# DA2_SCH_PAGE2.net
KiCad netlist of a schematic drawn in Altium Designer
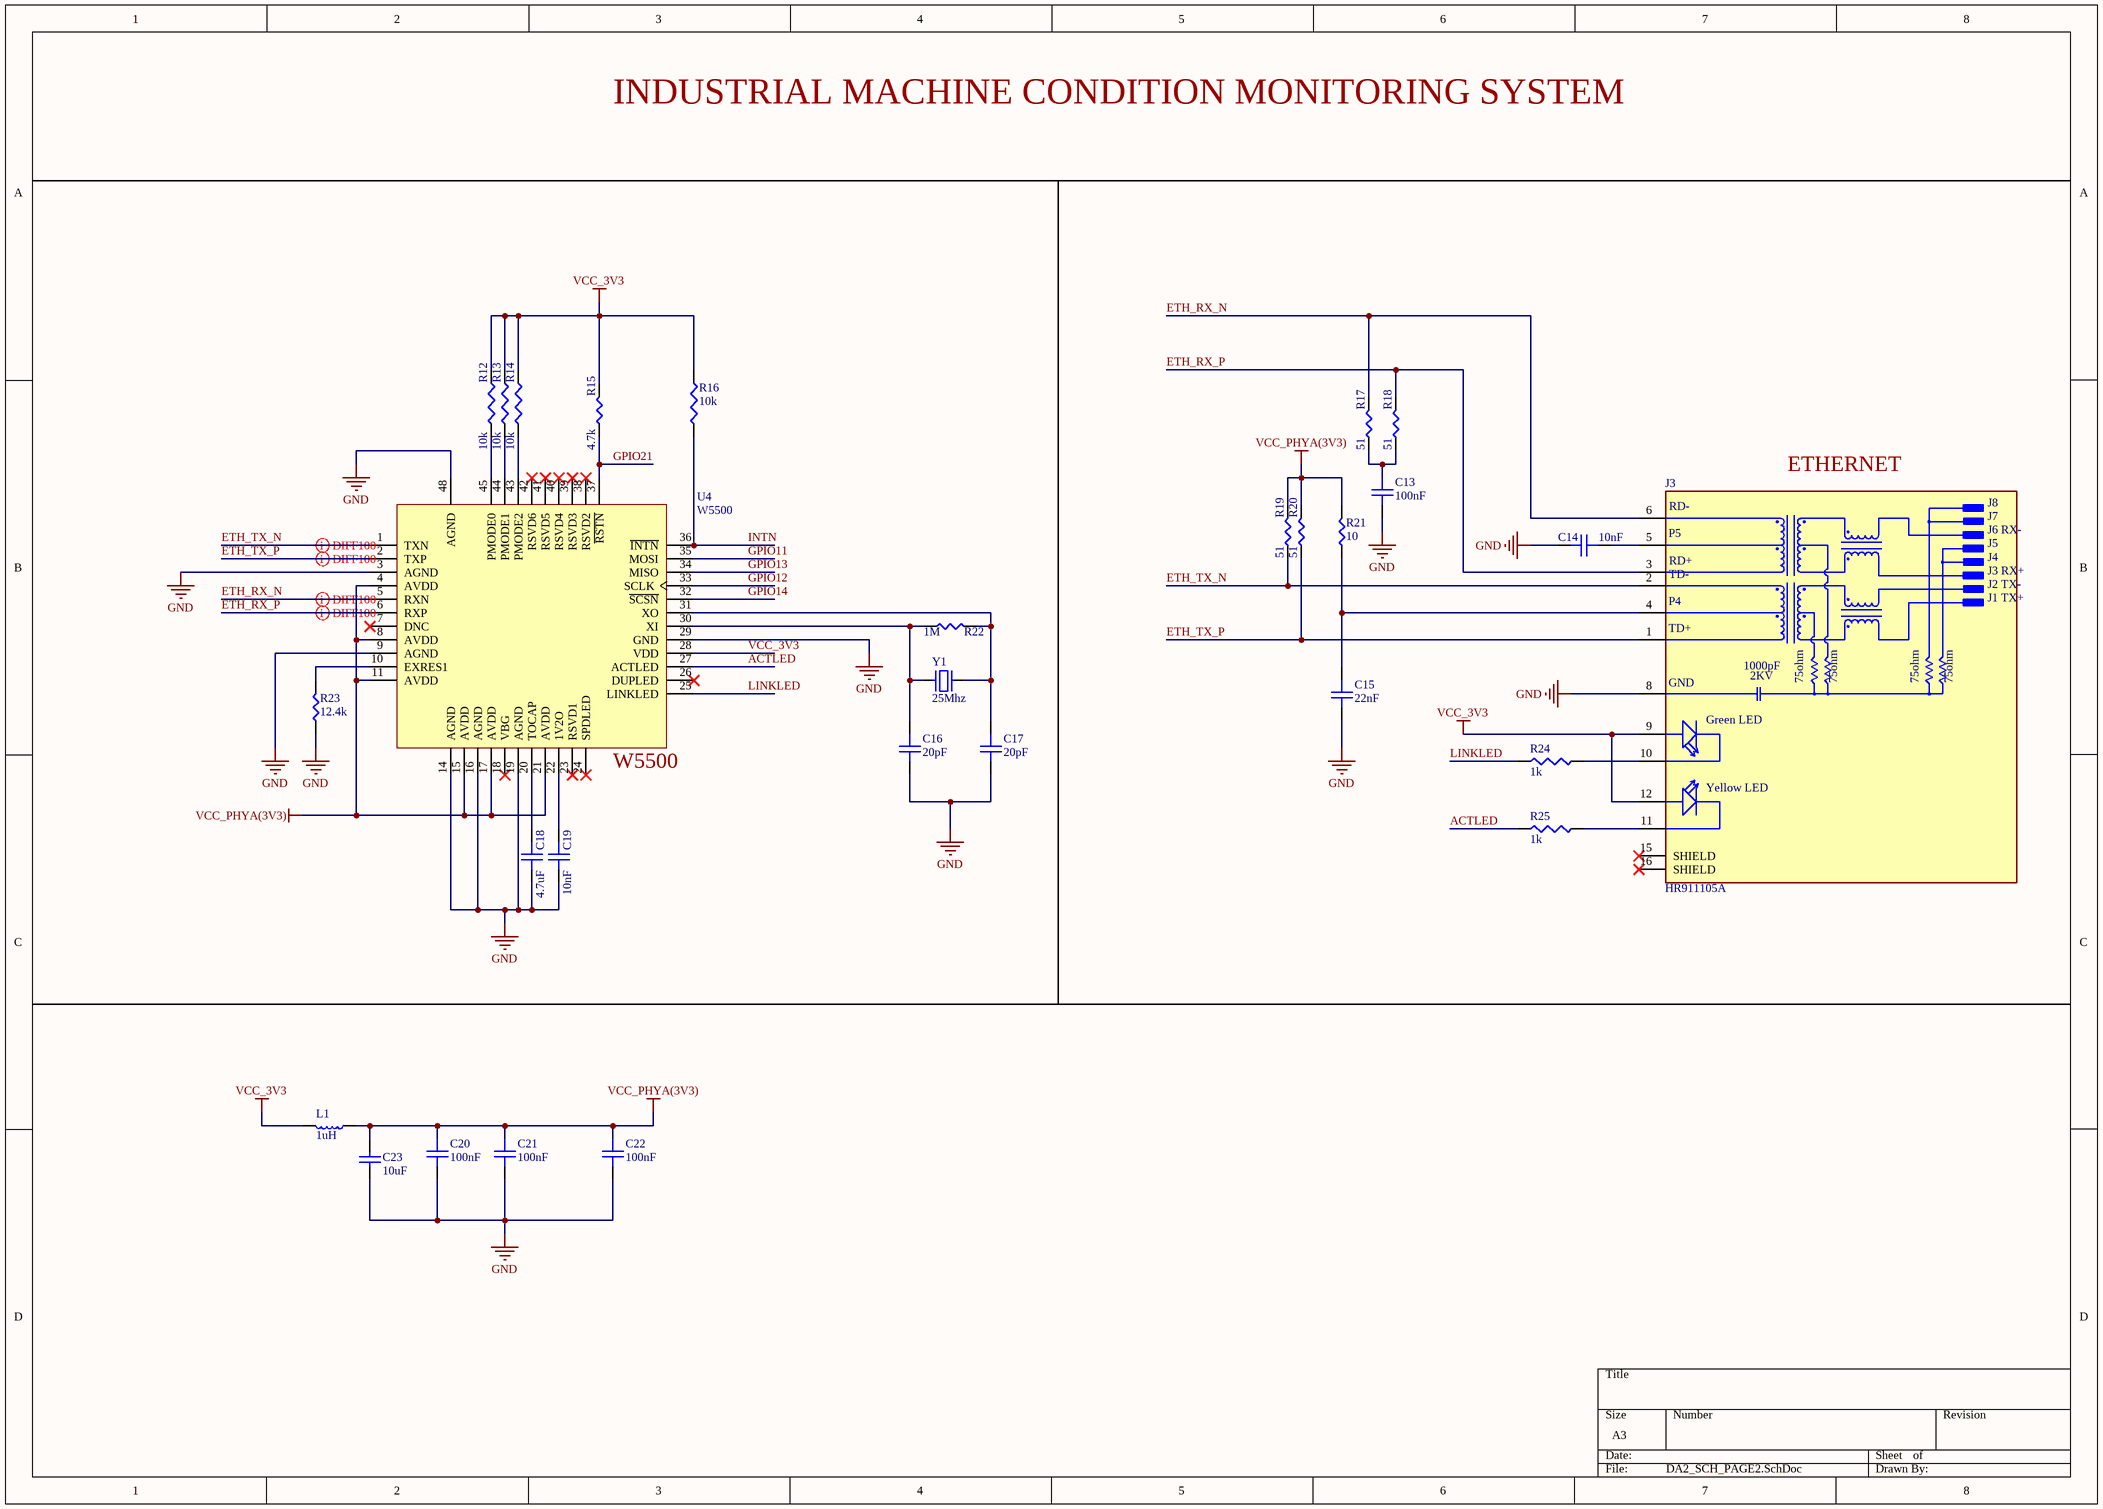
[diagram p0: DA2_SCH_PAGE2.SchDoc]

(export (version "E")
  (design (tool "Eeschema 10.0.6"))
  (components
    (comp (ref "C13")
      (value "100nF")
      (footprint "tu 0805")
      (description "Dán 0805")
      (libsource (lib "DA2") (part "Tu 100nF"))
    )
    (comp (ref "C14")
      (value "10nF")
      (footprint "tu 0805")
      (description "Dán 0805")
      (libsource (lib "DA2") (part "Tu 10nF"))
    )
    (comp (ref "C15")
      (value "22nF")
      (footprint "tu 0805")
      (description "Dán 0805")
      (libsource (lib "DA2") (part "Tu 22nF"))
    )
    (comp (ref "C16")
      (value "20pF")
      (footprint "tu 0805")
      (description "Dán 0805")
      (libsource (lib "DA2") (part "Tu  20pF"))
    )
    (comp (ref "C17")
      (value "20pF")
      (footprint "tu 0805")
      (description "Dán 0805")
      (libsource (lib "DA2") (part "Tu  20pF"))
    )
    (comp (ref "C18")
      (value "4.7uF")
      (footprint "Tu 0805")
      (description "Dán 0805")
      (libsource (lib "DA2") (part "Tu 4.7uF"))
    )
    (comp (ref "C19")
      (value "10nF")
      (footprint "tu 0805")
      (description "Dán 0805")
      (libsource (lib "DA2") (part "Tu 10nF"))
    )
    (comp (ref "C20")
      (value "100nF")
      (footprint "tu 0805")
      (description "Dán 0805")
      (libsource (lib "DA2") (part "Tu 100nF"))
    )
    (comp (ref "C21")
      (value "100nF")
      (footprint "tu 0805")
      (description "Dán 0805")
      (libsource (lib "DA2") (part "Tu 100nF"))
    )
    (comp (ref "C22")
      (value "100nF")
      (footprint "tu 0805")
      (description "Dán 0805")
      (libsource (lib "DA2") (part "Tu 100nF"))
    )
    (comp (ref "C23")
      (value "10uF")
      (footprint "Tu 0805")
      (description "Dán 0805")
      (fields
        (field (name "MANUFACTURER") "Samsung Electro-Mechanics")
        (field (name "MANUFACTURER PART NUMBER") "CL05A106MP5NUNC")
      )
      (libsource (lib "DA2") (part "Tu 10uF"))
    )
    (comp (ref "J3")
      (value "HR911105A")
      (footprint "HANRUN_HR911105A")
      (description "DIP RJ45 Connector;")
      (fields (field (name "MF") "hanrun"))
      (libsource (lib "Schlib1") (part "HR911105A"))
    )
    (comp (ref "L1")
      (value "1uH")
      (footprint "Tu 0805")
      (description "Dán 0805")
      (libsource (lib "DA2") (part "Cuon Cam 1uH"))
    )
    (comp (ref "R12")
      (value "10k")
      (footprint "Tro SMD 0805")
      (description "Dán 0805")
      (fields
        (field (name "MANUFACTURER") "Yageo Group")
        (field (name "MANUFACTURER PART NUMBER") "RC0402FR-0710KL")
      )
      (libsource (lib "DA2") (part "Tro 10k"))
    )
    (comp (ref "R13")
      (value "10k")
      (footprint "Tro SMD 0805")
      (description "Dán 0805")
      (fields
        (field (name "MANUFACTURER") "Yageo Group")
        (field (name "MANUFACTURER PART NUMBER") "RC0402FR-0710KL")
      )
      (libsource (lib "DA2") (part "Tro 10k"))
    )
    (comp (ref "R14")
      (value "10k")
      (footprint "Tro SMD 0805")
      (description "Dán 0805")
      (fields
        (field (name "MANUFACTURER") "Yageo Group")
        (field (name "MANUFACTURER PART NUMBER") "RC0402FR-0710KL")
      )
      (libsource (lib "DA2") (part "Tro 10k"))
    )
    (comp (ref "R15")
      (value "4.7k")
      (footprint "tro smd 0805")
      (description "Dán 0805")
      (libsource (lib "DA2") (part "Tro 4.7k"))
    )
    (comp (ref "R16")
      (value "10k")
      (footprint "Tro SMD 0805")
      (description "Dán 0805")
      (fields
        (field (name "MANUFACTURER") "Yageo Group")
        (field (name "MANUFACTURER PART NUMBER") "RC0402FR-0710KL")
      )
      (libsource (lib "DA2") (part "Tro 10k"))
    )
    (comp (ref "R17")
      (value "51")
      (footprint "tro smd 0805")
      (description "Dán 0805")
      (libsource (lib "DA2") (part "Tro 51"))
    )
    (comp (ref "R18")
      (value "51")
      (footprint "tro smd 0805")
      (description "Dán 0805")
      (libsource (lib "DA2") (part "Tro 51"))
    )
    (comp (ref "R19")
      (value "51")
      (footprint "tro smd 0805")
      (description "Dán 0805")
      (libsource (lib "DA2") (part "Tro 51"))
    )
    (comp (ref "R20")
      (value "51")
      (footprint "tro smd 0805")
      (description "Dán 0805")
      (libsource (lib "DA2") (part "Tro 51"))
    )
    (comp (ref "R21")
      (value "10")
      (footprint "tro smd 0805")
      (description "Dán 0805")
      (libsource (lib "DA2") (part "Tro 10"))
    )
    (comp (ref "R22")
      (value "1M")
      (footprint "tro smd 0805")
      (description "Dán 0805")
      (libsource (lib "DA2") (part "Tro 1M"))
    )
    (comp (ref "R23")
      (value "12.4k")
      (footprint "tro smd 0805")
      (description "Dán 0805")
      (libsource (lib "DA2") (part "Tro 12.4k"))
    )
    (comp (ref "R24")
      (value "1k")
      (footprint "Tro SMD 0805")
      (description "Dán 0805")
      (fields
        (field (name "MANUFACTURER") "Yageo Group")
        (field (name "MANUFACTURER PART NUMBER") "RC0402JR-071KL")
      )
      (libsource (lib "DA2") (part "Tro 1k"))
    )
    (comp (ref "R25")
      (value "1k")
      (footprint "Tro SMD 0805")
      (description "Dán 0805")
      (fields
        (field (name "MANUFACTURER") "Yageo Group")
        (field (name "MANUFACTURER PART NUMBER") "RC0402JR-071KL")
      )
      (libsource (lib "DA2") (part "Tro 1k"))
    )
    (comp (ref "U4")
      (value "W5500")
      (footprint "QFP50P900X900X160-48N")
      (description "Hardwired TCP/IP embedded Ethernet controller")
      (libsource (lib "Schlib1") (part "W5500"))
    )
    (comp (ref "Y1")
      (value "25Mhz")
      (footprint "XTAL 25.000MHz")
      (description "Crystal For all Crystal 2pin.")
      (libsource (lib "DA2") (part "Thach Anh 2 chan SMD 5032"))
    )
  )
  (nets
    (net (code "1") (name "/ACTLED") (class "Default")
      (node (ref "R25") (pin "1") (pinfunction "1_1") (pintype "passive"))
      (node (ref "U4") (pin "27") (pinfunction "ACTLED_27") (pintype "passive"))
    )
    (net (code "2") (name "/ETH_RX_N") (class "Default")
      (node (ref "J3") (pin "6") (pinfunction "RD-_6") (pintype "passive"))
      (node (ref "R17") (pin "2") (pinfunction "2_2") (pintype "passive"))
      (node (ref "U4") (pin "5") (pinfunction "RXN_5") (pintype "passive"))
    )
    (net (code "3") (name "/ETH_RX_P") (class "Default")
      (node (ref "J3") (pin "3") (pinfunction "RD+_3") (pintype "passive"))
      (node (ref "R18") (pin "2") (pinfunction "2_2") (pintype "passive"))
      (node (ref "U4") (pin "6") (pinfunction "RXP_6") (pintype "passive"))
    )
    (net (code "4") (name "/ETH_TX_N") (class "Default")
      (node (ref "J3") (pin "2") (pinfunction "TD-_2") (pintype "passive"))
      (node (ref "R19") (pin "1") (pinfunction "1_1") (pintype "passive"))
      (node (ref "U4") (pin "1") (pinfunction "TXN_1") (pintype "passive"))
    )
    (net (code "5") (name "/ETH_TX_P") (class "Default")
      (node (ref "J3") (pin "1") (pinfunction "TD+_1") (pintype "passive"))
      (node (ref "R20") (pin "1") (pinfunction "1_1") (pintype "passive"))
      (node (ref "U4") (pin "2") (pinfunction "TXP_2") (pintype "passive"))
    )
    (net (code "6") (name "/GPIO11") (class "Default")
      (node (ref "U4") (pin "35") (pinfunction "MOSI_35") (pintype "passive"))
    )
    (net (code "7") (name "/GPIO12") (class "Default")
      (node (ref "U4") (pin "33") (pinfunction "SCLK_33") (pintype "passive"))
    )
    (net (code "8") (name "/GPIO13") (class "Default")
      (node (ref "U4") (pin "34") (pinfunction "MISO_34") (pintype "passive"))
    )
    (net (code "9") (name "/GPIO14") (class "Default")
      (node (ref "U4") (pin "32") (pinfunction "~{SCSN}_32") (pintype "passive"))
    )
    (net (code "10") (name "/GPIO21") (class "Default")
      (node (ref "R15") (pin "1") (pinfunction "1_1") (pintype "passive"))
      (node (ref "U4") (pin "37") (pinfunction "~{RSTN}_37") (pintype "passive"))
    )
    (net (code "11") (name "/INTN") (class "Default")
      (node (ref "R16") (pin "1") (pinfunction "1_1") (pintype "passive"))
      (node (ref "U4") (pin "36") (pinfunction "~{INTN}_36") (pintype "passive"))
    )
    (net (code "12") (name "/LINKLED") (class "Default")
      (node (ref "R24") (pin "1") (pinfunction "1_1") (pintype "passive"))
      (node (ref "U4") (pin "25") (pinfunction "LINKLED_25") (pintype "passive"))
    )
    (net (code "13") (name "GND") (class "Default")
      (node (ref "C13") (pin "2") (pinfunction "2_2") (pintype "passive"))
      (node (ref "C14") (pin "2") (pinfunction "2_2") (pintype "passive"))
      (node (ref "C15") (pin "2") (pinfunction "2_2") (pintype "passive"))
      (node (ref "C16") (pin "2") (pinfunction "2_2") (pintype "passive"))
      (node (ref "C17") (pin "2") (pinfunction "2_2") (pintype "passive"))
      (node (ref "C18") (pin "2") (pinfunction "2_2") (pintype "passive"))
      (node (ref "C19") (pin "2") (pinfunction "2_2") (pintype "passive"))
      (node (ref "C20") (pin "2") (pinfunction "2_2") (pintype "passive"))
      (node (ref "C21") (pin "2") (pinfunction "2_2") (pintype "passive"))
      (node (ref "C22") (pin "2") (pinfunction "2_2") (pintype "passive"))
      (node (ref "C23") (pin "1") (pinfunction "1_1") (pintype "passive"))
      (node (ref "J3") (pin "8") (pinfunction "GND_8") (pintype "power_in"))
      (node (ref "R23") (pin "1") (pinfunction "1_1") (pintype "passive"))
      (node (ref "U4") (pin "14") (pinfunction "AGND_14") (pintype "passive"))
      (node (ref "U4") (pin "16") (pinfunction "AGND_16") (pintype "passive"))
      (node (ref "U4") (pin "19") (pinfunction "AGND_19") (pintype "passive"))
      (node (ref "U4") (pin "29") (pinfunction "GND_29") (pintype "passive"))
      (node (ref "U4") (pin "3") (pinfunction "AGND_3") (pintype "passive"))
      (node (ref "U4") (pin "48") (pinfunction "AGND_48") (pintype "passive"))
      (node (ref "U4") (pin "9") (pinfunction "AGND_9") (pintype "passive"))
    )
    (net (code "14") (name "Net-(C13-Pad1)") (class "Default")
      (node (ref "C13") (pin "1") (pinfunction "1_1") (pintype "passive"))
      (node (ref "R17") (pin "1") (pinfunction "1_1") (pintype "passive"))
      (node (ref "R18") (pin "1") (pinfunction "1_1") (pintype "passive"))
    )
    (net (code "15") (name "Net-(J3-GC)") (class "Default")
      (node (ref "J3") (pin "10") (pinfunction "GC_10") (pintype "passive"))
      (node (ref "R24") (pin "2") (pinfunction "2_2") (pintype "passive"))
    )
    (net (code "16") (name "Net-(J3-P4)") (class "Default")
      (node (ref "C15") (pin "1") (pinfunction "1_1") (pintype "passive"))
      (node (ref "J3") (pin "4") (pinfunction "P4_4") (pintype "passive"))
      (node (ref "R21") (pin "1") (pinfunction "1_1") (pintype "passive"))
    )
    (net (code "17") (name "Net-(J3-P5)") (class "Default")
      (node (ref "C14") (pin "1") (pinfunction "1_1") (pintype "passive"))
      (node (ref "J3") (pin "5") (pinfunction "P5_5") (pintype "passive"))
    )
    (net (code "18") (name "Net-(J3-YC)") (class "Default")
      (node (ref "J3") (pin "11") (pinfunction "YC_11") (pintype "passive"))
      (node (ref "R25") (pin "2") (pinfunction "2_2") (pintype "passive"))
    )
    (net (code "19") (name "Net-(U4-1V2O)") (class "Default")
      (node (ref "C19") (pin "1") (pinfunction "1_1") (pintype "passive"))
      (node (ref "U4") (pin "22") (pinfunction "1V2O_22") (pintype "passive"))
    )
    (net (code "20") (name "Net-(U4-EXRES1)") (class "Default")
      (node (ref "R23") (pin "2") (pinfunction "2_2") (pintype "passive"))
      (node (ref "U4") (pin "10") (pinfunction "EXRES1_10") (pintype "passive"))
    )
    (net (code "21") (name "Net-(U4-PMODE0)") (class "Default")
      (node (ref "R12") (pin "1") (pinfunction "1_1") (pintype "passive"))
      (node (ref "U4") (pin "45") (pinfunction "PMODE0_45") (pintype "passive"))
    )
    (net (code "22") (name "Net-(U4-PMODE1)") (class "Default")
      (node (ref "R13") (pin "1") (pinfunction "1_1") (pintype "passive"))
      (node (ref "U4") (pin "44") (pinfunction "PMODE1_44") (pintype "passive"))
    )
    (net (code "23") (name "Net-(U4-PMODE2)") (class "Default")
      (node (ref "R14") (pin "1") (pinfunction "1_1") (pintype "passive"))
      (node (ref "U4") (pin "43") (pinfunction "PMODE2_43") (pintype "passive"))
    )
    (net (code "24") (name "Net-(U4-TOCAP)") (class "Default")
      (node (ref "C18") (pin "1") (pinfunction "1_1") (pintype "passive"))
      (node (ref "U4") (pin "20") (pinfunction "TOCAP_20") (pintype "passive"))
    )
    (net (code "25") (name "Net-(U4-XI)") (class "Default")
      (node (ref "C16") (pin "1") (pinfunction "1_1") (pintype "passive"))
      (node (ref "R22") (pin "1") (pinfunction "1_1") (pintype "passive"))
      (node (ref "U4") (pin "30") (pinfunction "XI_30") (pintype "passive"))
      (node (ref "Y1") (pin "1") (pinfunction "1_1") (pintype "passive"))
    )
    (net (code "26") (name "Net-(U4-XO)") (class "Default")
      (node (ref "C17") (pin "1") (pinfunction "1_1") (pintype "passive"))
      (node (ref "R22") (pin "2") (pinfunction "2_2") (pintype "passive"))
      (node (ref "U4") (pin "31") (pinfunction "XO_31") (pintype "passive"))
      (node (ref "Y1") (pin "2") (pinfunction "2_2") (pintype "passive"))
    )
    (net (code "27") (name "VCC_3V3") (class "Default")
      (node (ref "J3") (pin "12") (pinfunction "YA_12") (pintype "passive"))
      (node (ref "J3") (pin "9") (pinfunction "GA_9") (pintype "passive"))
      (node (ref "L1") (pin "1") (pinfunction "1_1") (pintype "passive"))
      (node (ref "R12") (pin "2") (pinfunction "2_2") (pintype "passive"))
      (node (ref "R13") (pin "2") (pinfunction "2_2") (pintype "passive"))
      (node (ref "R14") (pin "2") (pinfunction "2_2") (pintype "passive"))
      (node (ref "R15") (pin "2") (pinfunction "2_2") (pintype "passive"))
      (node (ref "R16") (pin "2") (pinfunction "2_2") (pintype "passive"))
      (node (ref "U4") (pin "28") (pinfunction "VDD_28") (pintype "passive"))
    )
    (net (code "28") (name "VCC_PHYA(3V3)") (class "Default")
      (node (ref "C20") (pin "1") (pinfunction "1_1") (pintype "passive"))
      (node (ref "C21") (pin "1") (pinfunction "1_1") (pintype "passive"))
      (node (ref "C22") (pin "1") (pinfunction "1_1") (pintype "passive"))
      (node (ref "C23") (pin "2") (pinfunction "2_2") (pintype "passive"))
      (node (ref "L1") (pin "2") (pinfunction "2_2") (pintype "passive"))
      (node (ref "R19") (pin "2") (pinfunction "2_2") (pintype "passive"))
      (node (ref "R20") (pin "2") (pinfunction "2_2") (pintype "passive"))
      (node (ref "R21") (pin "2") (pinfunction "2_2") (pintype "passive"))
      (node (ref "U4") (pin "11") (pinfunction "AVDD_11") (pintype "passive"))
      (node (ref "U4") (pin "15") (pinfunction "AVDD_15") (pintype "passive"))
      (node (ref "U4") (pin "17") (pinfunction "AVDD_17") (pintype "passive"))
      (node (ref "U4") (pin "21") (pinfunction "AVDD_21") (pintype "passive"))
      (node (ref "U4") (pin "4") (pinfunction "AVDD_4") (pintype "passive"))
      (node (ref "U4") (pin "8") (pinfunction "AVDD_8") (pintype "passive"))
    )
    (net (code "29") (name "unconnected-(J3-SHIELD-Pad15)") (class "Default")
      (node (ref "J3") (pin "15") (pinfunction "SHIELD_15") (pintype "passive+no_connect"))
    )
    (net (code "30") (name "unconnected-(J3-SHIELD-Pad16)") (class "Default")
      (node (ref "J3") (pin "16") (pinfunction "SHIELD_16") (pintype "passive+no_connect"))
    )
    (net (code "31") (name "unconnected-(U4-DNC-Pad7)") (class "Default")
      (node (ref "U4") (pin "7") (pinfunction "DNC_7") (pintype "passive+no_connect"))
    )
    (net (code "32") (name "unconnected-(U4-DUPLED-Pad26)") (class "Default")
      (node (ref "U4") (pin "26") (pinfunction "DUPLED_26") (pintype "passive+no_connect"))
    )
    (net (code "33") (name "unconnected-(U4-RSVD1-Pad23)") (class "Default")
      (node (ref "U4") (pin "23") (pinfunction "RSVD1_23") (pintype "passive+no_connect"))
    )
    (net (code "34") (name "unconnected-(U4-RSVD2-Pad38)") (class "Default")
      (node (ref "U4") (pin "38") (pinfunction "RSVD2_38") (pintype "passive+no_connect"))
    )
    (net (code "35") (name "unconnected-(U4-RSVD3-Pad39)") (class "Default")
      (node (ref "U4") (pin "39") (pinfunction "RSVD3_39") (pintype "passive+no_connect"))
    )
    (net (code "36") (name "unconnected-(U4-RSVD4-Pad40)") (class "Default")
      (node (ref "U4") (pin "40") (pinfunction "RSVD4_40") (pintype "passive+no_connect"))
    )
    (net (code "37") (name "unconnected-(U4-RSVD5-Pad41)") (class "Default")
      (node (ref "U4") (pin "41") (pinfunction "RSVD5_41") (pintype "passive+no_connect"))
    )
    (net (code "38") (name "unconnected-(U4-RSVD6-Pad42)") (class "Default")
      (node (ref "U4") (pin "42") (pinfunction "RSVD6_42") (pintype "passive+no_connect"))
    )
    (net (code "39") (name "unconnected-(U4-SPDLED-Pad24)") (class "Default")
      (node (ref "U4") (pin "24") (pinfunction "SPDLED_24") (pintype "passive+no_connect"))
    )
    (net (code "40") (name "unconnected-(U4-VBG-Pad18)") (class "Default")
      (node (ref "U4") (pin "18") (pinfunction "VBG_18") (pintype "passive+no_connect"))
    )
  )
)
